# rgb_and_irdistance_side1.net
KiCad netlist of a schematic drawn in EAGLE
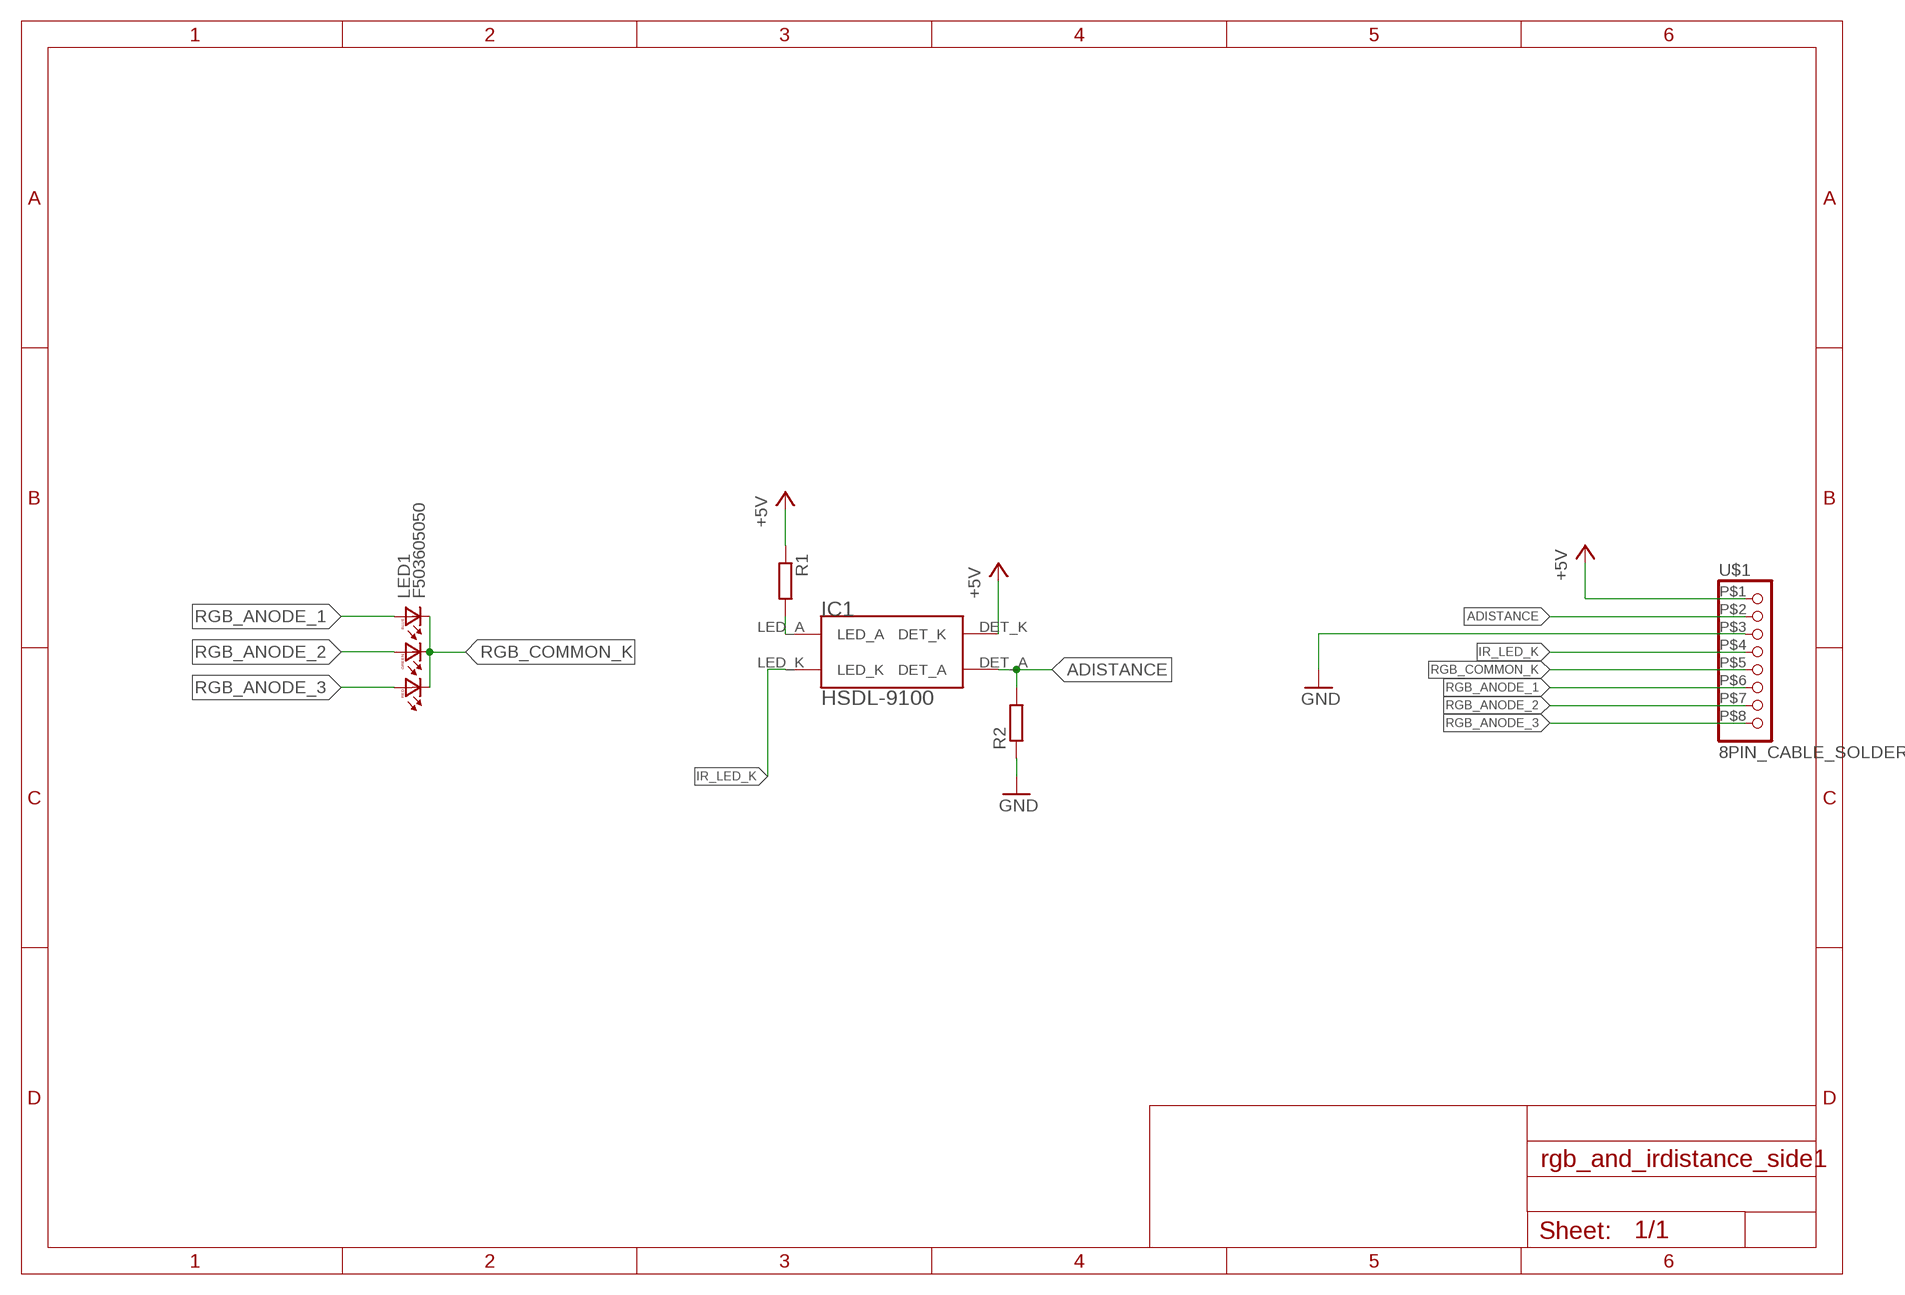
[diagram p0: schematic, sheet 1]

(export (version "E")
  (design (tool "Eeschema 10.0.6"))
  (components
    (comp (ref "IC1")
      (value "HSDL-9100")
      (footprint "eagle-import:HSDL-9100")
      (libsource (lib "eagle-import") (part "HSDL-9100"))
    )
    (comp (ref "LED1")
      (value "F503605050")
      (footprint "eagle-import:5050LED")
      (libsource (lib "eagle-import") (part "F503605050"))
    )
    (comp (ref "R1")
      (value "R-EU_M0805")
      (footprint "eagle-import:M0805")
      (libsource (lib "eagle-import") (part "R-EU_M0805"))
    )
    (comp (ref "R2")
      (value "R-EU_M0805")
      (footprint "eagle-import:M0805")
      (libsource (lib "eagle-import") (part "R-EU_M0805"))
    )
    (comp (ref "U$1")
      (value "8PIN_CABLE_SOLDER")
      (footprint "eagle-import:8PIN_CABLE_SOLDER")
      (libsource (lib "eagle-import") (part "8PIN_CABLE_SOLDER"))
    )
  )
  (nets
    (net (code "1") (name "+5V") (class "Default")
      (node (ref "IC1") (pin "DET_K") (pinfunction "DET_K_DET_K") (pintype "bidirectional"))
      (node (ref "R1") (pin "1") (pinfunction "1_1") (pintype "passive"))
      (node (ref "U$1") (pin "P$1") (pinfunction "1_P$1") (pintype "passive"))
    )
    (net (code "2") (name "ADISTANCE") (class "Default")
      (node (ref "IC1") (pin "DET_A") (pinfunction "DET_A_DET_A") (pintype "bidirectional"))
      (node (ref "R2") (pin "2") (pinfunction "2_2") (pintype "passive"))
      (node (ref "U$1") (pin "P$2") (pinfunction "2_P$2") (pintype "passive"))
    )
    (net (code "3") (name "GND") (class "Default")
      (node (ref "R2") (pin "1") (pinfunction "1_1") (pintype "passive"))
      (node (ref "U$1") (pin "P$3") (pinfunction "3_P$3") (pintype "passive"))
    )
    (net (code "4") (name "IR_LED_K") (class "Default")
      (node (ref "IC1") (pin "LED_K") (pinfunction "LED_K_LED_K") (pintype "bidirectional"))
      (node (ref "U$1") (pin "P$4") (pinfunction "4_P$4") (pintype "passive"))
    )
    (net (code "5") (name "Net-(IC1-PadLED_A)") (class "Default")
      (node (ref "IC1") (pin "LED_A") (pinfunction "LED_A_LED_A") (pintype "bidirectional"))
      (node (ref "R1") (pin "2") (pinfunction "2_2") (pintype "passive"))
    )
    (net (code "6") (name "RGB_ANODE_1") (class "Default")
      (node (ref "LED1") (pin "B1") (pinfunction "BA_B1") (pintype "passive"))
      (node (ref "U$1") (pin "P$6") (pinfunction "6_P$6") (pintype "passive"))
    )
    (net (code "7") (name "RGB_ANODE_2") (class "Default")
      (node (ref "LED1") (pin "G1") (pinfunction "GA_G1") (pintype "passive"))
      (node (ref "U$1") (pin "P$7") (pinfunction "7_P$7") (pintype "passive"))
    )
    (net (code "8") (name "RGB_ANODE_3") (class "Default")
      (node (ref "LED1") (pin "R1") (pinfunction "RA_R1") (pintype "passive"))
      (node (ref "U$1") (pin "P$8") (pinfunction "8_P$8") (pintype "passive"))
    )
    (net (code "9") (name "RGB_COMMON_K") (class "Default")
      (node (ref "LED1") (pin "B2") (pinfunction "BC_B2") (pintype "passive"))
      (node (ref "LED1") (pin "G2") (pinfunction "GC_G2") (pintype "passive"))
      (node (ref "LED1") (pin "R2") (pinfunction "RC_R2") (pintype "passive"))
      (node (ref "U$1") (pin "P$5") (pinfunction "5_P$5") (pintype "passive"))
    )
  )
)
